# contactor_connectors.net
KiCad netlist of a schematic drawn in Altium Designer
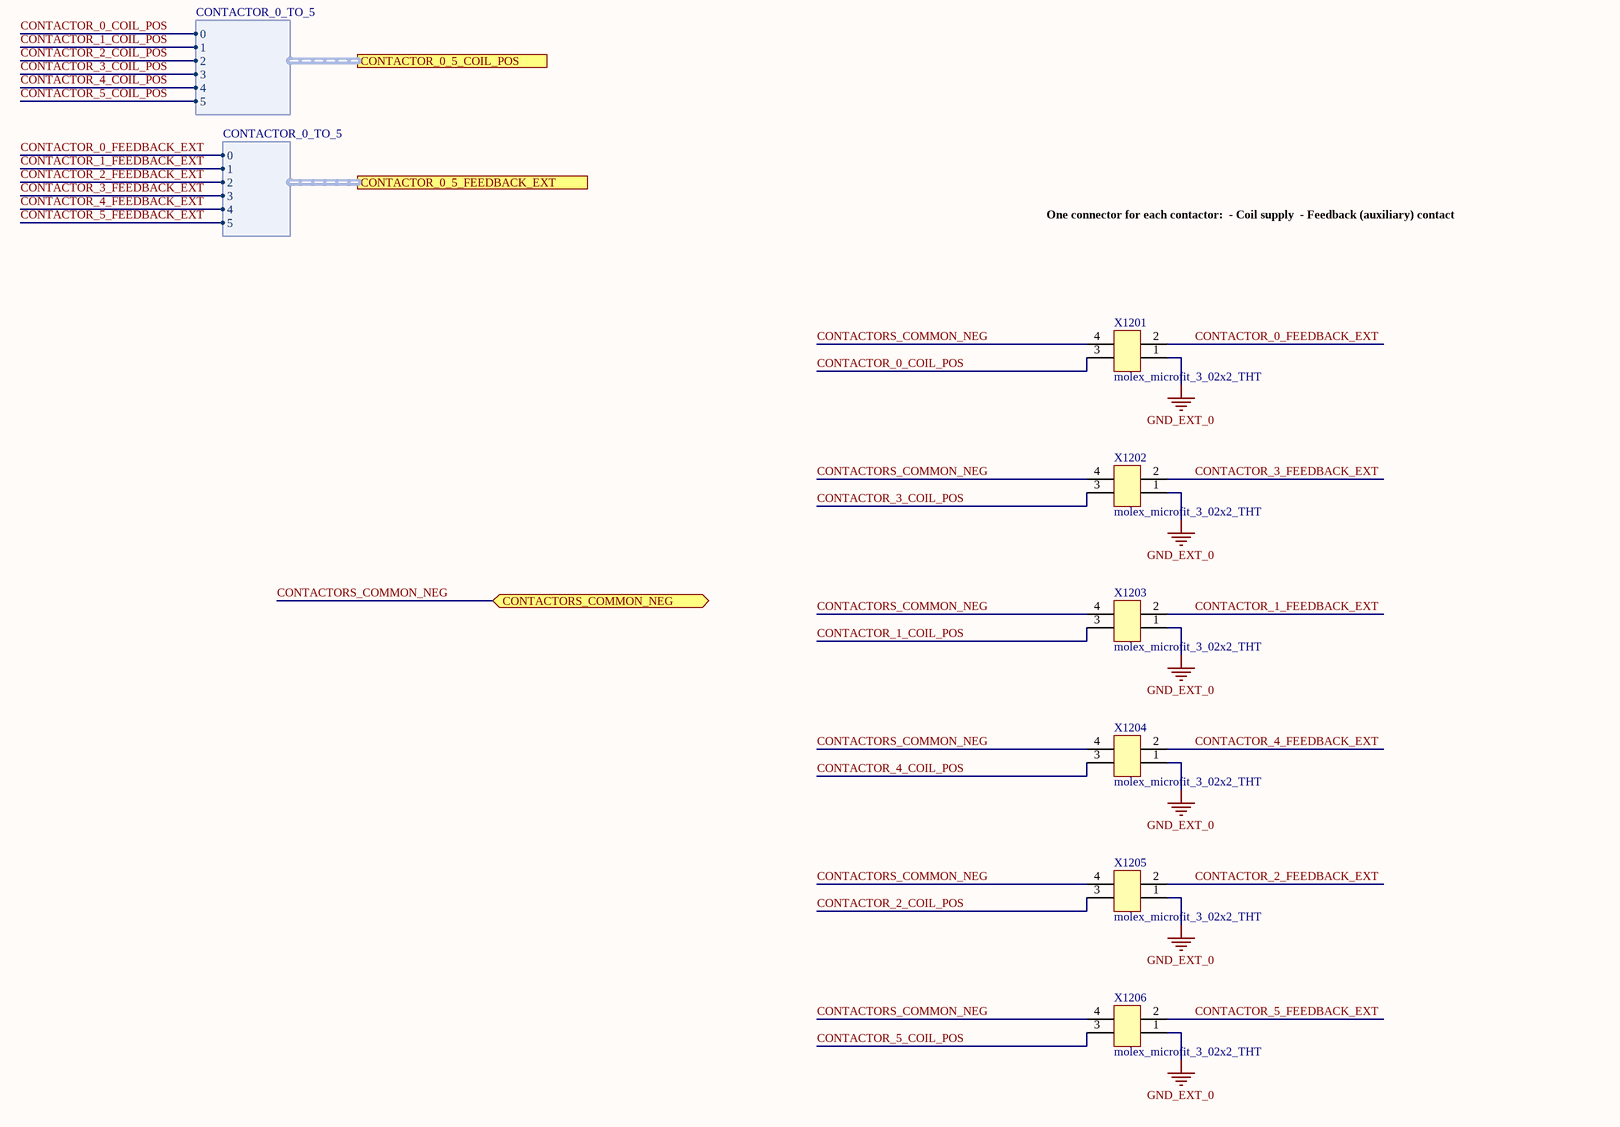
[diagram p0: contactor_connectors.SchDoc]

(export (version "E")
  (design (tool "Eeschema 10.0.6"))
  (components
    (comp (ref "X1201")
      (value "molex_microfit_3_02x2_THT")
      (footprint "MOLEX_MICROFIT_02x2_THT")
      (fields (field (name "MANUFACTURER") "Molex"))
      (libsource (lib "OE750") (part "X2x2"))
    )
    (comp (ref "X1202")
      (value "molex_microfit_3_02x2_THT")
      (footprint "MOLEX_MICROFIT_02x2_THT")
      (fields (field (name "MANUFACTURER") "Molex"))
      (libsource (lib "OE750") (part "X2x2"))
    )
    (comp (ref "X1203")
      (value "molex_microfit_3_02x2_THT")
      (footprint "MOLEX_MICROFIT_02x2_THT")
      (fields (field (name "MANUFACTURER") "Molex"))
      (libsource (lib "OE750") (part "X2x2"))
    )
    (comp (ref "X1204")
      (value "molex_microfit_3_02x2_THT")
      (footprint "MOLEX_MICROFIT_02x2_THT")
      (fields (field (name "MANUFACTURER") "Molex"))
      (libsource (lib "OE750") (part "X2x2"))
    )
    (comp (ref "X1205")
      (value "molex_microfit_3_02x2_THT")
      (footprint "MOLEX_MICROFIT_02x2_THT")
      (fields (field (name "MANUFACTURER") "Molex"))
      (libsource (lib "OE750") (part "X2x2"))
    )
    (comp (ref "X1206")
      (value "molex_microfit_3_02x2_THT")
      (footprint "MOLEX_MICROFIT_02x2_THT")
      (fields (field (name "MANUFACTURER") "Molex"))
      (libsource (lib "OE750") (part "X2x2"))
    )
  )
  (nets
    (net (code "2") (name "/CONTACTORS_COMMON_NEG") (class "Default")
      (node (ref "X1201") (pin "4") (pintype "passive"))
      (node (ref "X1202") (pin "4") (pintype "passive"))
      (node (ref "X1203") (pin "4") (pintype "passive"))
      (node (ref "X1204") (pin "4") (pintype "passive"))
      (node (ref "X1205") (pin "4") (pintype "passive"))
      (node (ref "X1206") (pin "4") (pintype "passive"))
    )
    (net (code "3") (name "/CONTACTOR_0_COIL_POS") (class "Default")
      (node (ref "X1201") (pin "3") (pintype "passive"))
    )
    (net (code "4") (name "/CONTACTOR_0_FEEDBACK_EXT") (class "Default")
      (node (ref "X1201") (pin "2") (pintype "passive"))
    )
    (net (code "5") (name "/CONTACTOR_1_COIL_POS") (class "Default")
      (node (ref "X1203") (pin "3") (pintype "passive"))
    )
    (net (code "6") (name "/CONTACTOR_1_FEEDBACK_EXT") (class "Default")
      (node (ref "X1203") (pin "2") (pintype "passive"))
    )
    (net (code "7") (name "/CONTACTOR_2_COIL_POS") (class "Default")
      (node (ref "X1205") (pin "3") (pintype "passive"))
    )
    (net (code "8") (name "/CONTACTOR_2_FEEDBACK_EXT") (class "Default")
      (node (ref "X1205") (pin "2") (pintype "passive"))
    )
    (net (code "9") (name "/CONTACTOR_3_COIL_POS") (class "Default")
      (node (ref "X1202") (pin "3") (pintype "passive"))
    )
    (net (code "10") (name "/CONTACTOR_3_FEEDBACK_EXT") (class "Default")
      (node (ref "X1202") (pin "2") (pintype "passive"))
    )
    (net (code "11") (name "/CONTACTOR_4_COIL_POS") (class "Default")
      (node (ref "X1204") (pin "3") (pintype "passive"))
    )
    (net (code "12") (name "/CONTACTOR_4_FEEDBACK_EXT") (class "Default")
      (node (ref "X1204") (pin "2") (pintype "passive"))
    )
    (net (code "13") (name "/CONTACTOR_5_COIL_POS") (class "Default")
      (node (ref "X1206") (pin "3") (pintype "passive"))
    )
    (net (code "14") (name "/CONTACTOR_5_FEEDBACK_EXT") (class "Default")
      (node (ref "X1206") (pin "2") (pintype "passive"))
    )
    (net (code "16") (name "GND_EXT_0") (class "Default")
      (node (ref "X1201") (pin "1") (pintype "passive"))
      (node (ref "X1202") (pin "1") (pintype "passive"))
      (node (ref "X1203") (pin "1") (pintype "passive"))
      (node (ref "X1204") (pin "1") (pintype "passive"))
      (node (ref "X1205") (pin "1") (pintype "passive"))
      (node (ref "X1206") (pin "1") (pintype "passive"))
    )
  )
)
